# Hand.net
KiCad netlist of a schematic drawn in EAGLE
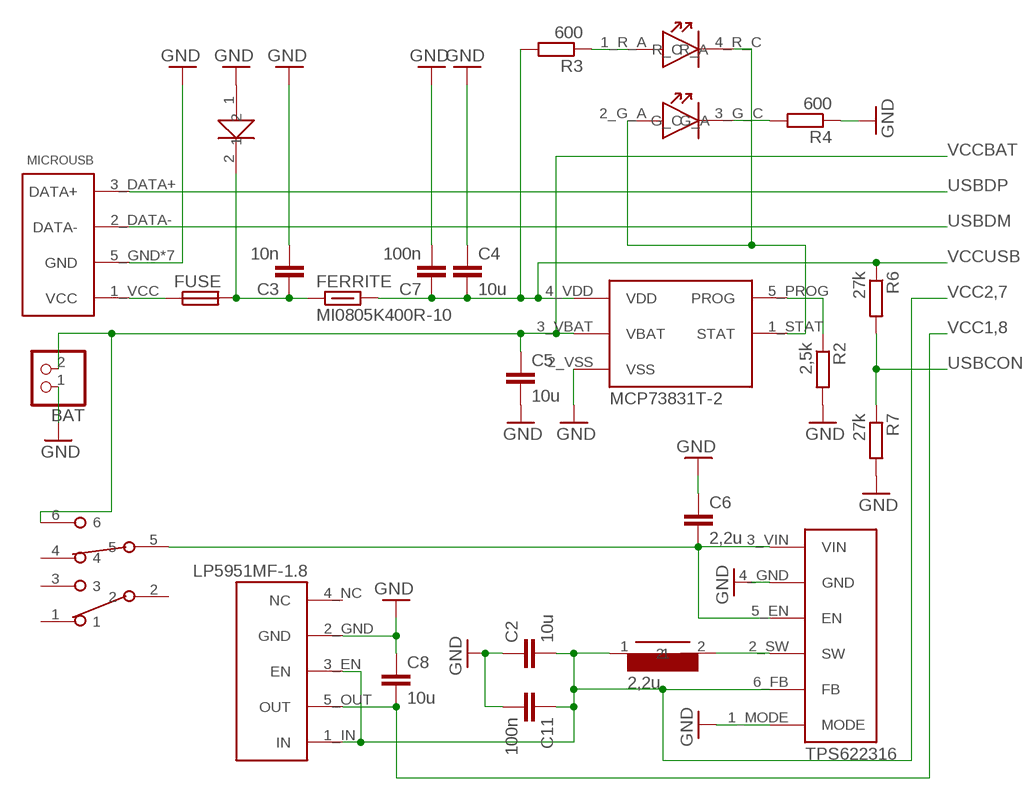
[diagram p0: schematic, sheet 1, part 1 of 2]
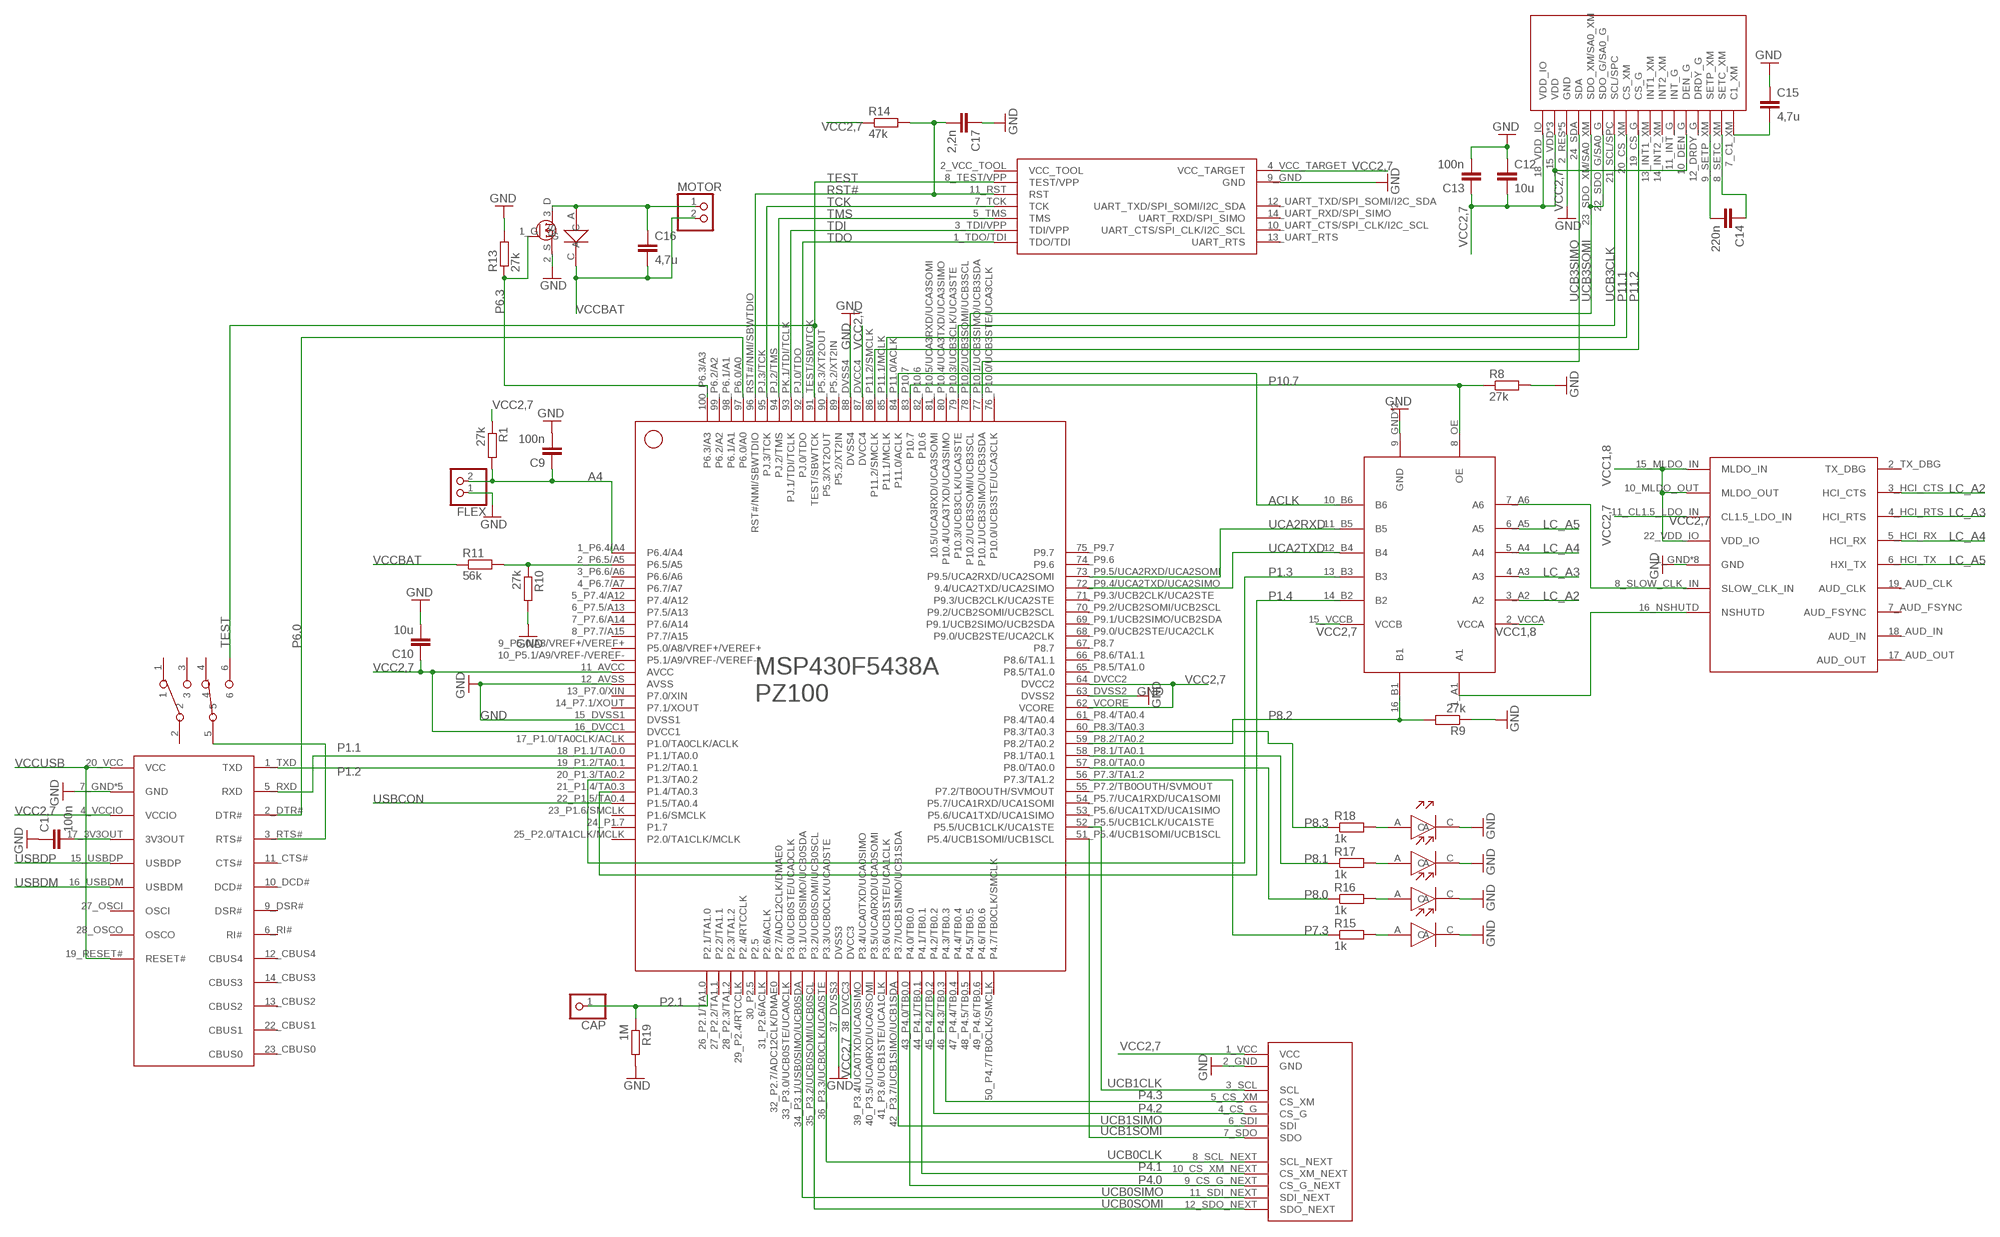
[diagram p1: schematic, sheet 1, part 2 of 2]

(export (version "E")
  (design (tool "Eeschema 10.0.6"))
  (components
    (comp (ref "BAT")
      (value "PINHD-1X2")
      (footprint "eagle-import:1X02")
      (libsource (lib "eagle-import") (part "PINHD-1X2"))
    )
    (comp (ref "C1")
      (value "100n")
      (footprint "eagle-import:C0402")
      (libsource (lib "eagle-import") (part "rclGlove_C-EUC0402"))
    )
    (comp (ref "C2")
      (value "10u")
      (footprint "eagle-import:C0805")
      (libsource (lib "eagle-import") (part "C-EUC0805"))
    )
    (comp (ref "C3")
      (value "10n")
      (footprint "eagle-import:C0402")
      (libsource (lib "eagle-import") (part "rclGlove_C-EUC0402"))
    )
    (comp (ref "C4")
      (value "10u")
      (footprint "eagle-import:C0805")
      (libsource (lib "eagle-import") (part "C-EUC0805"))
    )
    (comp (ref "C5")
      (value "10u")
      (footprint "eagle-import:C0805")
      (libsource (lib "eagle-import") (part "C-EUC0805"))
    )
    (comp (ref "C6")
      (value "2,2u")
      (footprint "eagle-import:C0805")
      (libsource (lib "eagle-import") (part "C-EUC0805"))
    )
    (comp (ref "C7")
      (value "100n")
      (footprint "eagle-import:C0402")
      (libsource (lib "eagle-import") (part "rclGlove_C-EUC0402"))
    )
    (comp (ref "C8")
      (value "10u")
      (footprint "eagle-import:C0805")
      (libsource (lib "eagle-import") (part "C-EUC0805"))
    )
    (comp (ref "C9")
      (value "100n")
      (footprint "eagle-import:C0402")
      (libsource (lib "eagle-import") (part "rclGlove_C-EUC0402"))
    )
    (comp (ref "C10")
      (value "10u")
      (footprint "eagle-import:C0805")
      (libsource (lib "eagle-import") (part "C-EUC0805"))
    )
    (comp (ref "C11")
      (value "100n")
      (footprint "eagle-import:C0402")
      (libsource (lib "eagle-import") (part "rclGlove_C-EUC0402"))
    )
    (comp (ref "C12")
      (value "10u")
      (footprint "eagle-import:C0805")
      (libsource (lib "eagle-import") (part "C-EUC0805"))
    )
    (comp (ref "C13")
      (value "100n")
      (footprint "eagle-import:C0402")
      (libsource (lib "eagle-import") (part "rclGlove_C-EUC0402"))
    )
    (comp (ref "C14")
      (value "220n")
      (footprint "eagle-import:C0402")
      (libsource (lib "eagle-import") (part "rclGlove_C-EUC0402"))
    )
    (comp (ref "C15")
      (value "4,7u")
      (footprint "eagle-import:C0805")
      (libsource (lib "eagle-import") (part "C-EUC0805"))
    )
    (comp (ref "C16")
      (value "4,7u")
      (footprint "eagle-import:C0805")
      (libsource (lib "eagle-import") (part "C-EUC0805"))
    )
    (comp (ref "C17")
      (value "2,2n")
      (footprint "eagle-import:C0603")
      (libsource (lib "eagle-import") (part "rclGlove_C-EUC0603"))
    )
    (comp (ref "CAP")
      (value "PINHD-1X1")
      (footprint "eagle-import:1X01")
      (libsource (lib "eagle-import") (part "PINHD-1X1"))
    )
    (comp (ref "FERRITE")
      (value "MI0805K400R-10")
      (footprint "eagle-import:R0603")
      (libsource (lib "eagle-import") (part "FERRITER0603"))
    )
    (comp (ref "FLEX")
      (value "PINHD-1X2")
      (footprint "eagle-import:1X02")
      (libsource (lib "eagle-import") (part "PINHD-1X2"))
    )
    (comp (ref "FUSE")
      (value "SICHERUNG")
      (footprint "eagle-import:C0603")
      (libsource (lib "eagle-import") (part "SICHERUNG"))
    )
    (comp (ref "IMU_OUT")
      (value "IMU-BUCHSE-OUT")
      (footprint "eagle-import:OUT")
      (libsource (lib "eagle-import") (part "IMU-BUCHSE-OUT"))
    )
    (comp (ref "LP5951MF-1.8")
      (value "VDDIOREGLER-SC70")
      (footprint "eagle-import:SC70")
      (libsource (lib "eagle-import") (part "VDDIOREGLER-SC70"))
    )
    (comp (ref "MCP73831T-2")
      (value "MCP73831/2-SOT-23-5")
      (footprint "eagle-import:SOT-23-5")
      (libsource (lib "eagle-import") (part "MCP73831/2-SOT-23-5"))
    )
    (comp (ref "MICROUSB")
      (value "MICRO_USB-PCB")
      (footprint "eagle-import:PCB")
      (libsource (lib "eagle-import") (part "MICRO_USB-PCB"))
    )
    (comp (ref "MOTOR")
      (value "PINHD-1X2")
      (footprint "eagle-import:1X02")
      (libsource (lib "eagle-import") (part "PINHD-1X2"))
    )
    (comp (ref "R1")
      (value "27k")
      (footprint "eagle-import:R0402")
      (libsource (lib "eagle-import") (part "R-EU_R0402"))
    )
    (comp (ref "R2")
      (value "2,5k")
      (footprint "eagle-import:R0402")
      (libsource (lib "eagle-import") (part "R-EU_R0402"))
    )
    (comp (ref "R3")
      (value "600")
      (footprint "eagle-import:R0402")
      (libsource (lib "eagle-import") (part "R-EU_R0402"))
    )
    (comp (ref "R4")
      (value "600")
      (footprint "eagle-import:R0402")
      (libsource (lib "eagle-import") (part "R-EU_R0402"))
    )
    (comp (ref "R6")
      (value "27k")
      (footprint "eagle-import:R0402")
      (libsource (lib "eagle-import") (part "R-EU_R0402"))
    )
    (comp (ref "R7")
      (value "27k")
      (footprint "eagle-import:R0402")
      (libsource (lib "eagle-import") (part "R-EU_R0402"))
    )
    (comp (ref "R8")
      (value "27k")
      (footprint "eagle-import:R0402")
      (libsource (lib "eagle-import") (part "R-EU_R0402"))
    )
    (comp (ref "R9")
      (value "27k")
      (footprint "eagle-import:R0402")
      (libsource (lib "eagle-import") (part "R-EU_R0402"))
    )
    (comp (ref "R10")
      (value "27k")
      (footprint "eagle-import:R0402")
      (libsource (lib "eagle-import") (part "R-EU_R0402"))
    )
    (comp (ref "R11")
      (value "56k")
      (footprint "eagle-import:R0402")
      (libsource (lib "eagle-import") (part "R-EU_R0402"))
    )
    (comp (ref "R13")
      (value "27k")
      (footprint "eagle-import:R0402")
      (libsource (lib "eagle-import") (part "R-EU_R0402"))
    )
    (comp (ref "R14")
      (value "47k")
      (footprint "eagle-import:R0402")
      (libsource (lib "eagle-import") (part "R-EU_R0402"))
    )
    (comp (ref "R15")
      (value "1k")
      (footprint "eagle-import:R0402")
      (libsource (lib "eagle-import") (part "R-EU_R0402"))
    )
    (comp (ref "R16")
      (value "1k")
      (footprint "eagle-import:R0402")
      (libsource (lib "eagle-import") (part "R-EU_R0402"))
    )
    (comp (ref "R17")
      (value "1k")
      (footprint "eagle-import:R0402")
      (libsource (lib "eagle-import") (part "R-EU_R0402"))
    )
    (comp (ref "R18")
      (value "1k")
      (footprint "eagle-import:R0402")
      (libsource (lib "eagle-import") (part "R-EU_R0402"))
    )
    (comp (ref "R19")
      (value "1M")
      (footprint "eagle-import:R0402")
      (libsource (lib "eagle-import") (part "R-EU_R0402"))
    )
    (comp (ref "SPULE")
      (value "2,2u")
      (footprint "eagle-import:C0603")
      (libsource (lib "eagle-import") (part "SPULE"))
    )
    (comp (ref "TPS622316")
      (value "SCHALTREGLER-R-PUSON-N6")
      (footprint "eagle-import:R-PUSON-N6")
      (libsource (lib "eagle-import") (part "SCHALTREGLER-R-PUSON-N6"))
    )
    (comp (ref "U$1")
      (value "FT232R-SSOP-28")
      (footprint "eagle-import:SSOP-28")
      (libsource (lib "eagle-import") (part "FT232R-SSOP-28"))
    )
    (comp (ref "U$2")
      (value "LSM9DS0-LGA-24")
      (footprint "eagle-import:LGA-24")
      (libsource (lib "eagle-import") (part "LSM9DS0-LGA-24"))
    )
    (comp (ref "U$4")
      (value "PAN132X")
      (footprint "eagle-import:BOARD")
      (libsource (lib "eagle-import") (part "PAN132X"))
    )
    (comp (ref "U$5")
      (value "MSP430BT5190-PZ100")
      (footprint "eagle-import:PZ100")
      (libsource (lib "eagle-import") (part "MSP430BT5190-PZ100"))
    )
    (comp (ref "U$7")
      (value "LED-PCB")
      (footprint "eagle-import:PCB")
      (libsource (lib "eagle-import") (part "LED-PCB"))
    )
    (comp (ref "U$8")
      (value "LADE-MOSFET-SOC-23")
      (footprint "eagle-import:SOT-23")
      (libsource (lib "eagle-import") (part "LADE-MOSFET-SOC-23"))
    )
    (comp (ref "U$9")
      (value "FREILAUFDIODE")
      (footprint "eagle-import:FEILAUFDIODE")
      (libsource (lib "eagle-import") (part "FREILAUFDIODE"))
    )
    (comp (ref "U$11")
      (value "ANSCHALTER-PACKAGE")
      (footprint "eagle-import:PACKAGE")
      (libsource (lib "eagle-import") (part "ANSCHALTER-PACKAGE"))
    )
    (comp (ref "U$12")
      (value "ANSCHALTER-PACKAGE")
      (footprint "eagle-import:PACKAGE")
      (libsource (lib "eagle-import") (part "ANSCHALTER-PACKAGE"))
    )
    (comp (ref "U$13")
      (value "LOGIKPEGELWANDLER-6CH")
      (footprint "eagle-import:R-PVQFN-N16")
      (libsource (lib "eagle-import") (part "LOGIKPEGELWANDLER-6CH"))
    )
    (comp (ref "U$15")
      (value "LEDMINI")
      (footprint "eagle-import:LEDMINI")
      (libsource (lib "eagle-import") (part "LEDMINI"))
    )
    (comp (ref "U$16")
      (value "JTAG-BUCHSE")
      (footprint "eagle-import:BUCHSE")
      (libsource (lib "eagle-import") (part "JTAG-BUCHSE"))
    )
    (comp (ref "U$17")
      (value "LEDMINI")
      (footprint "eagle-import:LEDMINI")
      (libsource (lib "eagle-import") (part "LEDMINI"))
    )
    (comp (ref "U$18")
      (value "LEDMINI")
      (footprint "eagle-import:LEDMINI")
      (libsource (lib "eagle-import") (part "LEDMINI"))
    )
    (comp (ref "U$19")
      (value "LEDMINI")
      (footprint "eagle-import:LEDMINI")
      (libsource (lib "eagle-import") (part "LEDMINI"))
    )
    (comp (ref "U$20")
      (value "DIODE-C0603")
      (footprint "eagle-import:C0603")
      (libsource (lib "eagle-import") (part "DIODE-C0603"))
    )
  )
  (nets
    (net (code "1") (name "/A4") (class "Default")
      (node (ref "C9") (pin "1") (pinfunction "1_1") (pintype "passive"))
      (node (ref "FLEX") (pin "2") (pinfunction "2_2") (pintype "passive"))
      (node (ref "R1") (pin "2") (pinfunction "2_2") (pintype "passive"))
      (node (ref "U$5") (pin "1_P6.4/A4") (pinfunction "P6.4/A4_1_P6.4/A4") (pintype "bidirectional"))
    )
    (net (code "2") (name "/ACLK") (class "Default")
      (node (ref "U$13") (pin "10_B6") (pinfunction "B6_10_B6") (pintype "bidirectional"))
      (node (ref "U$5") (pin "84_P11.0/ACLK") (pinfunction "P11.0/ACLK_84_P11.0/ACLK") (pintype "bidirectional"))
    )
    (net (code "3") (name "/LC_A2") (class "Default")
      (node (ref "U$13") (pin "3_A2") (pinfunction "A2_3_A2") (pintype "bidirectional"))
      (node (ref "U$4") (pin "3_HCI_CTS") (pinfunction "HCI_CTS_3_HCI_CTS") (pintype "bidirectional"))
    )
    (net (code "4") (name "/LC_A3") (class "Default")
      (node (ref "U$13") (pin "4_A3") (pinfunction "A3_4_A3") (pintype "bidirectional"))
      (node (ref "U$4") (pin "4_HCI_RTS") (pinfunction "HCI_RTS_4_HCI_RTS") (pintype "bidirectional"))
    )
    (net (code "5") (name "/LC_A4") (class "Default")
      (node (ref "U$13") (pin "5_A4") (pinfunction "A4_5_A4") (pintype "bidirectional"))
      (node (ref "U$4") (pin "5_HCI_RX") (pinfunction "HCI_RX_5_HCI_RX") (pintype "bidirectional"))
    )
    (net (code "6") (name "/LC_A5") (class "Default")
      (node (ref "U$13") (pin "6_A5") (pinfunction "A5_6_A5") (pintype "bidirectional"))
      (node (ref "U$4") (pin "6_HCI_TX") (pinfunction "HXI_TX_6_HCI_TX") (pintype "bidirectional"))
    )
    (net (code "7") (name "/P1.1") (class "Default")
      (node (ref "U$1") (pin "5_RXD") (pinfunction "RXD_5_RXD") (pintype "bidirectional"))
      (node (ref "U$5") (pin "18_P1.1/TA0.0") (pinfunction "P1.1/TA0.0_18_P1.1/TA0.0") (pintype "bidirectional"))
    )
    (net (code "8") (name "/P1.2") (class "Default")
      (node (ref "U$1") (pin "1_TXD") (pinfunction "TXD_1_TXD") (pintype "bidirectional"))
      (node (ref "U$5") (pin "19_P1.2/TA0.1") (pinfunction "P1.2/TA0.1_19_P1.2/TA0.1") (pintype "bidirectional"))
    )
    (net (code "9") (name "/P1.3") (class "Default")
      (node (ref "U$13") (pin "13_B3") (pinfunction "B3_13_B3") (pintype "bidirectional"))
      (node (ref "U$5") (pin "20_P1.3/TA0.2") (pinfunction "P1.3/TA0.2_20_P1.3/TA0.2") (pintype "bidirectional"))
    )
    (net (code "10") (name "/P1.4") (class "Default")
      (node (ref "U$13") (pin "14_B2") (pinfunction "B2_14_B2") (pintype "bidirectional"))
      (node (ref "U$5") (pin "21_P1.4/TA0.3") (pinfunction "P1.4/TA0.3_21_P1.4/TA0.3") (pintype "bidirectional"))
    )
    (net (code "11") (name "/P2.1") (class "Default")
      (node (ref "CAP") (pin "1") (pinfunction "1_1") (pintype "passive"))
      (node (ref "R19") (pin "1") (pinfunction "1_1") (pintype "passive"))
      (node (ref "U$5") (pin "26_P2.1/TA1.0") (pinfunction "P2.1/TA1.0_26_P2.1/TA1.0") (pintype "bidirectional"))
    )
    (net (code "12") (name "/P4.0") (class "Default")
      (node (ref "IMU_OUT") (pin "9_CS_G_NEXT") (pinfunction "CS_G_NEXT_9_CS_G_NEXT") (pintype "bidirectional"))
      (node (ref "U$5") (pin "43_P4.0/TB0.0") (pinfunction "P4.0/TB0.0_43_P4.0/TB0.0") (pintype "bidirectional"))
    )
    (net (code "13") (name "/P4.1") (class "Default")
      (node (ref "IMU_OUT") (pin "10_CS_XM_NEXT") (pinfunction "CS_XM_NEXT_10_CS_XM_NEXT") (pintype "bidirectional"))
      (node (ref "U$5") (pin "44_P4.1/TB0.1") (pinfunction "P4.1/TB0.1_44_P4.1/TB0.1") (pintype "bidirectional"))
    )
    (net (code "14") (name "/P4.2") (class "Default")
      (node (ref "IMU_OUT") (pin "4_CS_G") (pinfunction "CS_G_4_CS_G") (pintype "bidirectional"))
      (node (ref "U$5") (pin "45_P4.2/TB0.2") (pinfunction "P4.2/TB0.2_45_P4.2/TB0.2") (pintype "bidirectional"))
    )
    (net (code "15") (name "/P4.3") (class "Default")
      (node (ref "IMU_OUT") (pin "5_CS_XM") (pinfunction "CS_XM_5_CS_XM") (pintype "bidirectional"))
      (node (ref "U$5") (pin "46_P4.3/TB0.3") (pinfunction "P4.3/TB0.3_46_P4.3/TB0.3") (pintype "bidirectional"))
    )
    (net (code "16") (name "/P6.0") (class "Default")
      (node (ref "U$1") (pin "2_DTR#") (pinfunction "DTR#_2_DTR#") (pintype "bidirectional"))
      (node (ref "U$5") (pin "97_P6.0/A0") (pinfunction "P6.0/A0_97_P6.0/A0") (pintype "bidirectional"))
    )
    (net (code "17") (name "/P6.3") (class "Default")
      (node (ref "R13") (pin "1") (pinfunction "1_1") (pintype "passive"))
      (node (ref "U$5") (pin "100_P6.3/A3") (pinfunction "P6.3/A3_100_P6.3/A3") (pintype "bidirectional"))
      (node (ref "U$8") (pin "1_G") (pinfunction "G_1_G") (pintype "bidirectional"))
    )
    (net (code "18") (name "/P7.3") (class "Default")
      (node (ref "R15") (pin "1") (pinfunction "1_1") (pintype "passive"))
      (node (ref "U$5") (pin "56_P7.3/TA1.2") (pinfunction "P7.3/TA1.2_56_P7.3/TA1.2") (pintype "bidirectional"))
    )
    (net (code "19") (name "/P8.0") (class "Default")
      (node (ref "R16") (pin "1") (pinfunction "1_1") (pintype "passive"))
      (node (ref "U$5") (pin "57_P8.0/TA0.0") (pinfunction "P8.0/TA0.0_57_P8.0/TA0.0") (pintype "bidirectional"))
    )
    (net (code "20") (name "/P8.1") (class "Default")
      (node (ref "R17") (pin "1") (pinfunction "1_1") (pintype "passive"))
      (node (ref "U$5") (pin "58_P8.1/TA0.1") (pinfunction "P8.1/TA0.1_58_P8.1/TA0.1") (pintype "bidirectional"))
    )
    (net (code "21") (name "/P8.2") (class "Default")
      (node (ref "R9") (pin "2") (pinfunction "2_2") (pintype "passive"))
      (node (ref "U$13") (pin "16_B1") (pinfunction "B1_16_B1") (pintype "bidirectional"))
      (node (ref "U$5") (pin "59_P8.2/TA0.2") (pinfunction "P8.2/TA0.2_59_P8.2/TA0.2") (pintype "bidirectional"))
    )
    (net (code "22") (name "/P8.3") (class "Default")
      (node (ref "R18") (pin "1") (pinfunction "1_1") (pintype "passive"))
      (node (ref "U$5") (pin "60_P8.3/TA0.3") (pinfunction "P8.3/TA0.3_60_P8.3/TA0.3") (pintype "bidirectional"))
    )
    (net (code "23") (name "/P10.7") (class "Default")
      (node (ref "R8") (pin "1") (pinfunction "1_1") (pintype "passive"))
      (node (ref "U$13") (pin "8_OE") (pinfunction "OE_8_OE") (pintype "bidirectional"))
      (node (ref "U$5") (pin "83_P10.7") (pinfunction "P10.7_83_P10.7") (pintype "bidirectional"))
    )
    (net (code "24") (name "/P11.1") (class "Default")
      (node (ref "U$2") (pin "20_CS_XM") (pinfunction "CS_XM_20_CS_XM") (pintype "bidirectional"))
      (node (ref "U$5") (pin "85_P11.1/MCLK") (pinfunction "P11.1/MCLK_85_P11.1/MCLK") (pintype "bidirectional"))
    )
    (net (code "25") (name "/P11.2") (class "Default")
      (node (ref "U$2") (pin "19_CS_G") (pinfunction "CS_G_19_CS_G") (pintype "bidirectional"))
      (node (ref "U$5") (pin "86_P11.2/SMCLK") (pinfunction "P11.2/SMCLK_86_P11.2/SMCLK") (pintype "bidirectional"))
    )
    (net (code "26") (name "/RST#") (class "Default")
      (node (ref "C17") (pin "2") (pinfunction "2_2") (pintype "passive"))
      (node (ref "R14") (pin "2") (pinfunction "2_2") (pintype "passive"))
      (node (ref "U$16") (pin "11_RST") (pinfunction "RST_11_RST") (pintype "bidirectional"))
      (node (ref "U$5") (pin "96_RST#/NMI/SBWTDIO") (pinfunction "RST#/NMI/SBWTDIO_96_RST#/NMI/SBWTDIO") (pintype "bidirectional"))
    )
    (net (code "27") (name "/TCK") (class "Default")
      (node (ref "U$16") (pin "7_TCK") (pinfunction "TCK_7_TCK") (pintype "bidirectional"))
      (node (ref "U$5") (pin "95_PJ.3/TCK") (pinfunction "PJ.3/TCK_95_PJ.3/TCK") (pintype "bidirectional"))
    )
    (net (code "28") (name "/TDI") (class "Default")
      (node (ref "U$16") (pin "3_TDI/VPP") (pinfunction "TDI/VPP_3_TDI/VPP") (pintype "bidirectional"))
      (node (ref "U$5") (pin "93_PK.1/TDI/TCLK") (pinfunction "PJ.1/TDI/TCLK_93_PK.1/TDI/TCLK") (pintype "bidirectional"))
    )
    (net (code "29") (name "/TDO") (class "Default")
      (node (ref "U$16") (pin "1_TDO/TDI") (pinfunction "TDO/TDI_1_TDO/TDI") (pintype "bidirectional"))
      (node (ref "U$5") (pin "92_PJ.0/TDO") (pinfunction "PJ.0/TDO_92_PJ.0/TDO") (pintype "bidirectional"))
    )
    (net (code "30") (name "/TEST") (class "Default")
      (node (ref "U$11") (pin "6") (pinfunction "6_6") (pintype "bidirectional"))
      (node (ref "U$16") (pin "8_TEST/VPP") (pinfunction "TEST/VPP_8_TEST/VPP") (pintype "bidirectional"))
      (node (ref "U$5") (pin "91_TEST/SBWTCK") (pinfunction "TEST/SBWTCK_91_TEST/SBWTCK") (pintype "bidirectional"))
    )
    (net (code "31") (name "/TMS") (class "Default")
      (node (ref "U$16") (pin "5_TMS") (pinfunction "TMS_5_TMS") (pintype "bidirectional"))
      (node (ref "U$5") (pin "94_PJ.2/TMS") (pinfunction "PJ.2/TMS_94_PJ.2/TMS") (pintype "bidirectional"))
    )
    (net (code "32") (name "/UCA2RXD") (class "Default")
      (node (ref "U$13") (pin "11_B5") (pinfunction "B5_11_B5") (pintype "bidirectional"))
      (node (ref "U$5") (pin "73_P9.5/UCA2RXD/UCA2SOMI") (pinfunction "P9.5/UCA2RXD/UCA2SOMI_73_P9.5/UCA2RXD/UCA2SOMI") (pintype "bidirectional"))
    )
    (net (code "33") (name "/UCA2TXD") (class "Default")
      (node (ref "U$13") (pin "12_B4") (pinfunction "B4_12_B4") (pintype "bidirectional"))
      (node (ref "U$5") (pin "72_P9.4/UCA2TXD/UCA2SIMO") (pinfunction "9.4/UCA2TXD/UCA2SIMO_72_P9.4/UCA2TXD/UCA2SIMO") (pintype "bidirectional"))
    )
    (net (code "34") (name "/UCB0CLK") (class "Default")
      (node (ref "IMU_OUT") (pin "8_SCL_NEXT") (pinfunction "SCL_NEXT_8_SCL_NEXT") (pintype "bidirectional"))
      (node (ref "U$5") (pin "36_P3.3/UCB0CLK/UCA0STE") (pinfunction "P3.3/UCB0CLK/UCA0STE_36_P3.3/UCB0CLK/UCA0STE") (pintype "bidirectional"))
    )
    (net (code "35") (name "/UCB0SIMO") (class "Default")
      (node (ref "IMU_OUT") (pin "11_SDI_NEXT") (pinfunction "SDI_NEXT_11_SDI_NEXT") (pintype "bidirectional"))
      (node (ref "U$5") (pin "34_P3.1/USB0SIMO/UCB0SDA") (pinfunction "P3.1/UCB0SIMO/UCB0SDA_34_P3.1/USB0SIMO/UCB0SDA") (pintype "bidirectional"))
    )
    (net (code "36") (name "/UCB0SOMI") (class "Default")
      (node (ref "IMU_OUT") (pin "12_SDO_NEXT") (pinfunction "SDO_NEXT_12_SDO_NEXT") (pintype "bidirectional"))
      (node (ref "U$5") (pin "35_P3.2/UCB0SOMI/UCB0SCL") (pinfunction "P3.2/UCB0SOMI/UCB0SCL_35_P3.2/UCB0SOMI/UCB0SCL") (pintype "bidirectional"))
    )
    (net (code "37") (name "/UCB1CLK") (class "Default")
      (node (ref "IMU_OUT") (pin "3_SCL") (pinfunction "SCL_3_SCL") (pintype "bidirectional"))
      (node (ref "U$5") (pin "52_P5.5/UCB1CLK/UCA1STE") (pinfunction "P5.5/UCB1CLK/UCA1STE_52_P5.5/UCB1CLK/UCA1STE") (pintype "bidirectional"))
    )
    (net (code "38") (name "/UCB1SIMO") (class "Default")
      (node (ref "IMU_OUT") (pin "6_SDI") (pinfunction "SDI_6_SDI") (pintype "bidirectional"))
      (node (ref "U$5") (pin "42_P3.7/UCB1SIMO/UCB1SDA") (pinfunction "P3.7/UCB1SIMO/UCB1SDA_42_P3.7/UCB1SIMO/UCB1SDA") (pintype "bidirectional"))
    )
    (net (code "39") (name "/UCB1SOMI") (class "Default")
      (node (ref "IMU_OUT") (pin "7_SDO") (pinfunction "SDO_7_SDO") (pintype "bidirectional"))
      (node (ref "U$5") (pin "51_P5.4/UCB1SOMI/UCB1SCL") (pinfunction "P5.4/UCB1SOMI/UCB1SCL_51_P5.4/UCB1SOMI/UCB1SCL") (pintype "bidirectional"))
    )
    (net (code "40") (name "/UCB3CLK") (class "Default")
      (node (ref "U$2") (pin "21_SCL/SPC") (pinfunction "SCL/SPC_21_SCL/SPC") (pintype "bidirectional"))
      (node (ref "U$5") (pin "79_P10.3/UCB3CLK/UCA3STE") (pinfunction "P10.3/UCB3CLK/UCA3STE_79_P10.3/UCB3CLK/UCA3STE") (pintype "bidirectional"))
    )
    (net (code "41") (name "/UCB3SIMO") (class "Default")
      (node (ref "U$2") (pin "24_SDA") (pinfunction "SDA_24_SDA") (pintype "bidirectional"))
      (node (ref "U$5") (pin "77_P10.1/UCB3SIMO/UCB3SDA") (pinfunction "P10.1/UCB3SIMO/UCB3SDA_77_P10.1/UCB3SIMO/UCB3SDA") (pintype "bidirectional"))
    )
    (net (code "42") (name "/UCB3SOMI") (class "Default")
      (node (ref "U$2") (pin "22_SDO_G/SA0_G") (pinfunction "SDO_G/SA0_G_22_SDO_G/SA0_G") (pintype "bidirectional"))
      (node (ref "U$2") (pin "23_SDO_XM/SA0_XM") (pinfunction "SDO_XM/SA0_XM_23_SDO_XM/SA0_XM") (pintype "bidirectional"))
      (node (ref "U$5") (pin "78_P10.2/UCB3SOMI/UCB3SCL") (pinfunction "P10.2/UCB3SOMI/UCB3SCL_78_P10.2/UCB3SOMI/UCB3SCL") (pintype "bidirectional"))
    )
    (net (code "43") (name "/USBCON") (class "Default")
      (node (ref "R6") (pin "2") (pinfunction "2_2") (pintype "passive"))
      (node (ref "R7") (pin "1") (pinfunction "1_1") (pintype "passive"))
      (node (ref "U$5") (pin "22_P1.5/TA0.4") (pinfunction "P1.5/TA0.4_22_P1.5/TA0.4") (pintype "bidirectional"))
    )
    (net (code "44") (name "/USBDM") (class "Default")
      (node (ref "MICROUSB") (pin "2_DATA-") (pinfunction "DATA-_2_DATA-") (pintype "bidirectional"))
      (node (ref "U$1") (pin "16_USBDM") (pinfunction "USBDM_16_USBDM") (pintype "bidirectional"))
    )
    (net (code "45") (name "/USBDP") (class "Default")
      (node (ref "MICROUSB") (pin "3_DATA+") (pinfunction "DATA+_3_DATA+") (pintype "bidirectional"))
      (node (ref "U$1") (pin "15_USBDP") (pinfunction "USBDP_15_USBDP") (pintype "bidirectional"))
    )
    (net (code "46") (name "/VCC1,8") (class "Default")
      (node (ref "C8") (pin "2") (pinfunction "2_2") (pintype "passive"))
      (node (ref "LP5951MF-1.8") (pin "5_OUT") (pinfunction "OUT_5_OUT") (pintype "bidirectional"))
      (node (ref "U$13") (pin "2_VCCA") (pinfunction "VCCA_2_VCCA") (pintype "bidirectional"))
      (node (ref "U$4") (pin "10_MLDO_OUT") (pinfunction "MLDO_OUT_10_MLDO_OUT") (pintype "bidirectional"))
      (node (ref "U$4") (pin "15_MLDO_IN") (pinfunction "MLDO_IN_15_MLDO_IN") (pintype "bidirectional"))
      (node (ref "U$4") (pin "22_VDD_IO") (pinfunction "VDD_IO_22_VDD_IO") (pintype "bidirectional"))
    )
    (net (code "47") (name "/VCC2,7") (class "Default")
      (node (ref "C10") (pin "1") (pinfunction "1_1") (pintype "passive"))
      (node (ref "C11") (pin "1") (pinfunction "1_1") (pintype "passive"))
      (node (ref "C12") (pin "2") (pinfunction "2_2") (pintype "passive"))
      (node (ref "C13") (pin "1") (pinfunction "1_1") (pintype "passive"))
      (node (ref "C2") (pin "2") (pinfunction "2_2") (pintype "passive"))
      (node (ref "IMU_OUT") (pin "1_VCC") (pinfunction "VCC_1_VCC") (pintype "bidirectional"))
      (node (ref "LP5951MF-1.8") (pin "1_IN") (pinfunction "IN_1_IN") (pintype "bidirectional"))
      (node (ref "LP5951MF-1.8") (pin "3_EN") (pinfunction "EN_3_EN") (pintype "bidirectional"))
      (node (ref "R1") (pin "1") (pinfunction "1_1") (pintype "passive"))
      (node (ref "R14") (pin "1") (pinfunction "1_1") (pintype "passive"))
      (node (ref "SPULE") (pin "1") (pinfunction "1_1") (pintype "bidirectional"))
      (node (ref "TPS622316") (pin "6_FB") (pinfunction "FB_6_FB") (pintype "bidirectional"))
      (node (ref "U$1") (pin "4_VCCIO") (pinfunction "VCCIO_4_VCCIO") (pintype "bidirectional"))
      (node (ref "U$13") (pin "15_VCCB") (pinfunction "VCCB_15_VCCB") (pintype "bidirectional"))
      (node (ref "U$16") (pin "4_VCC_TARGET") (pinfunction "VCC_TARGET_4_VCC_TARGET") (pintype "bidirectional"))
      (node (ref "U$2") (pin "10_DEN_G") (pinfunction "DEN_G_10_DEN_G") (pintype "bidirectional"))
      (node (ref "U$2") (pin "15_VDD") (pinfunction "VDD_15_VDD") (pintype "bidirectional"))
      (node (ref "U$2") (pin "16_VDD") (pinfunction "VDD_16_VDD") (pintype "bidirectional"))
      (node (ref "U$2") (pin "17_VDD") (pinfunction "VDD_17_VDD") (pintype "bidirectional"))
      (node (ref "U$2") (pin "18_VDD_IO") (pinfunction "VDD_IO_18_VDD_IO") (pintype "bidirectional"))
      (node (ref "U$4") (pin "11_CL1.5_LDO_IN") (pinfunction "CL1.5_LDO_IN_11_CL1.5_LDO_IN") (pintype "bidirectional"))
      (node (ref "U$5") (pin "11_AVCC") (pinfunction "AVCC_11_AVCC") (pintype "bidirectional"))
      (node (ref "U$5") (pin "16_DVCC1") (pinfunction "DVCC1_16_DVCC1") (pintype "bidirectional"))
      (node (ref "U$5") (pin "38_DVCC3") (pinfunction "DVCC3_38_DVCC3") (pintype "bidirectional"))
      (node (ref "U$5") (pin "62_VCORE") (pinfunction "VCORE_62_VCORE") (pintype "bidirectional"))
      (node (ref "U$5") (pin "64_DVCC2") (pinfunction "DVCC2_64_DVCC2") (pintype "bidirectional"))
      (node (ref "U$5") (pin "87_DVCC4") (pinfunction "DVCC4_87_DVCC4") (pintype "bidirectional"))
    )
    (net (code "48") (name "/VCCBAT") (class "Default")
      (node (ref "BAT") (pin "2") (pinfunction "2_2") (pintype "passive"))
      (node (ref "C16") (pin "2") (pinfunction "2_2") (pintype "passive"))
      (node (ref "C5") (pin "1") (pinfunction "1_1") (pintype "passive"))
      (node (ref "MCP73831T-2") (pin "3_VBAT") (pinfunction "VBAT_3_VBAT") (pintype "bidirectional"))
      (node (ref "MOTOR") (pin "2") (pinfunction "2_2") (pintype "passive"))
      (node (ref "R11") (pin "1") (pinfunction "1_1") (pintype "passive"))
      (node (ref "U$12") (pin "6") (pinfunction "6_6") (pintype "bidirectional"))
      (node (ref "U$9") (pin "C") (pinfunction "C_C") (pintype "bidirectional"))
    )
    (net (code "49") (name "/VCCUSB") (class "Default")
      (node (ref "C4") (pin "2") (pinfunction "2_2") (pintype "passive"))
      (node (ref "C7") (pin "1") (pinfunction "1_1") (pintype "passive"))
      (node (ref "FERRITE") (pin "2") (pinfunction "2_2") (pintype "passive"))
      (node (ref "MCP73831T-2") (pin "4_VDD") (pinfunction "VDD_4_VDD") (pintype "bidirectional"))
      (node (ref "R3") (pin "2") (pinfunction "2_2") (pintype "passive"))
      (node (ref "R6") (pin "1") (pinfunction "1_1") (pintype "passive"))
      (node (ref "U$1") (pin "19_RESET#") (pinfunction "RESET#_19_RESET#") (pintype "bidirectional"))
      (node (ref "U$1") (pin "20_VCC") (pinfunction "VCC_20_VCC") (pintype "bidirectional"))
    )
    (net (code "50") (name "GND") (class "Default")
      (node (ref "BAT") (pin "1") (pinfunction "1_1") (pintype "passive"))
      (node (ref "C1") (pin "1") (pinfunction "1_1") (pintype "passive"))
      (node (ref "C10") (pin "2") (pinfunction "2_2") (pintype "passive"))
      (node (ref "C11") (pin "2") (pinfunction "2_2") (pintype "passive"))
      (node (ref "C12") (pin "1") (pinfunction "1_1") (pintype "passive"))
      (node (ref "C13") (pin "2") (pinfunction "2_2") (pintype "passive"))
      (node (ref "C15") (pin "1") (pinfunction "1_1") (pintype "passive"))
      (node (ref "C17") (pin "1") (pinfunction "1_1") (pintype "passive"))
      (node (ref "C2") (pin "1") (pinfunction "1_1") (pintype "passive"))
      (node (ref "C3") (pin "2") (pinfunction "2_2") (pintype "passive"))
      (node (ref "C4") (pin "1") (pinfunction "1_1") (pintype "passive"))
      (node (ref "C5") (pin "2") (pinfunction "2_2") (pintype "passive"))
      (node (ref "C6") (pin "1") (pinfunction "1_1") (pintype "passive"))
      (node (ref "C7") (pin "2") (pinfunction "2_2") (pintype "passive"))
      (node (ref "C8") (pin "1") (pinfunction "1_1") (pintype "passive"))
      (node (ref "C9") (pin "2") (pinfunction "2_2") (pintype "passive"))
      (node (ref "FLEX") (pin "1") (pinfunction "1_1") (pintype "passive"))
      (node (ref "IMU_OUT") (pin "2_GND") (pinfunction "GND_2_GND") (pintype "bidirectional"))
      (node (ref "LP5951MF-1.8") (pin "2_GND") (pinfunction "GND_2_GND") (pintype "bidirectional"))
      (node (ref "MCP73831T-2") (pin "2_VSS") (pinfunction "VSS_2_VSS") (pintype "bidirectional"))
      (node (ref "MICROUSB") (pin "5_GND") (pinfunction "GND_5_GND") (pintype "bidirectional"))
      (node (ref "MICROUSB") (pin "EP_1") (pinfunction "GND_EP_1") (pintype "bidirectional"))
      (node (ref "MICROUSB") (pin "EP_2") (pinfunction "GND_EP_2") (pintype "bidirectional"))
      (node (ref "MICROUSB") (pin "EP_3") (pinfunction "GND_EP_3") (pintype "bidirectional"))
      (node (ref "MICROUSB") (pin "EP_4") (pinfunction "GND_EP_4") (pintype "bidirectional"))
      (node (ref "MICROUSB") (pin "P$1") (pinfunction "GND_P$1") (pintype "bidirectional"))
      (node (ref "MICROUSB") (pin "P$2") (pinfunction "GND_P$2") (pintype "bidirectional"))
      (node (ref "R10") (pin "2") (pinfunction "2_2") (pintype "passive"))
      (node (ref "R13") (pin "2") (pinfunction "2_2") (pintype "passive"))
      (node (ref "R19") (pin "2") (pinfunction "2_2") (pintype "passive"))
      (node (ref "R2") (pin "2") (pinfunction "2_2") (pintype "passive"))
      (node (ref "R4") (pin "1") (pinfunction "1_1") (pintype "passive"))
      (node (ref "R7") (pin "2") (pinfunction "2_2") (pintype "passive"))
      (node (ref "R8") (pin "2") (pinfunction "2_2") (pintype "passive"))
      (node (ref "R9") (pin "1") (pinfunction "1_1") (pintype "passive"))
      (node (ref "TPS622316") (pin "1_MODE") (pinfunction "MODE_1_MODE") (pintype "bidirectional"))
      (node (ref "TPS622316") (pin "4_GND") (pinfunction "GND_4_GND") (pintype "bidirectional"))
      (node (ref "U$1") (pin "18_GND") (pinfunction "GND_18_GND") (pintype "bidirectional"))
      (node (ref "U$1") (pin "21_GND") (pinfunction "GND_21_GND") (pintype "bidirectional"))
      (node (ref "U$1") (pin "25_AGND") (pinfunction "GND_25_AGND") (pintype "bidirectional"))
      (node (ref "U$1") (pin "26_TEST") (pinfunction "GND_26_TEST") (pintype "bidirectional"))
      (node (ref "U$1") (pin "7_GND") (pinfunction "GND_7_GND") (pintype "bidirectional"))
      (node (ref "U$13") (pin "9_GND") (pinfunction "GND_9_GND") (pintype "bidirectional"))
      (node (ref "U$13") (pin "PAD") (pinfunction "GND_PAD") (pintype "bidirectional"))
      (node (ref "U$15") (pin "C") (pinfunction "C_C") (pintype "bidirectional"))
      (node (ref "U$16") (pin "9_GND") (pinfunction "GND_9_GND") (pintype "bidirectional"))
      (node (ref "U$17") (pin "C") (pinfunction "C_C") (pintype "bidirectional"))
      (node (ref "U$18") (pin "C") (pinfunction "C_C") (pintype "bidirectional"))
      (node (ref "U$19") (pin "C") (pinfunction "C_C") (pintype "bidirectional"))
      (node (ref "U$2") (pin "2_RES") (pinfunction "GND_2_RES") (pintype "bidirectional"))
      (node (ref "U$2") (pin "3_RES") (pinfunction "GND_3_RES") (pintype "bidirectional"))
      (node (ref "U$2") (pin "4_RES") (pinfunction "GND_4_RES") (pintype "bidirectional"))
      (node (ref "U$2") (pin "5_GND") (pinfunction "GND_5_GND") (pintype "bidirectional"))
      (node (ref "U$2") (pin "6_GND") (pinfunction "GND_6_GND") (pintype "bidirectional"))
      (node (ref "U$20") (pin "1") (pinfunction "1_1") (pintype "bidirectional"))
      (node (ref "U$4") (pin "12_GND") (pinfunction "GND_12_GND") (pintype "bidirectional"))
      (node (ref "U$4") (pin "14_GND") (pinfunction "GND_14_GND") (pintype "bidirectional"))
      (node (ref "U$4") (pin "1_GND") (pinfunction "GND_1_GND") (pintype "bidirectional"))
      (node (ref "U$4") (pin "20_GND") (pinfunction "GND_20_GND") (pintype "bidirectional"))
      (node (ref "U$4") (pin "A_GND") (pinfunction "GND_A_GND") (pintype "bidirectional"))
      (node (ref "U$4") (pin "B_GND") (pinfunction "GND_B_GND") (pintype "bidirectional"))
      (node (ref "U$4") (pin "C_GND") (pinfunction "GND_C_GND") (pintype "bidirectional"))
      (node (ref "U$4") (pin "D_GND") (pinfunction "GND_D_GND") (pintype "bidirectional"))
      (node (ref "U$5") (pin "12_AVSS") (pinfunction "AVSS_12_AVSS") (pintype "bidirectional"))
      (node (ref "U$5") (pin "15_DVSS1") (pinfunction "DVSS1_15_DVSS1") (pintype "bidirectional"))
      (node (ref "U$5") (pin "37_DVSS3") (pinfunction "DVSS3_37_DVSS3") (pintype "bidirectional"))
      (node (ref "U$5") (pin "63_DVSS2") (pinfunction "DVSS2_63_DVSS2") (pintype "bidirectional"))
      (node (ref "U$5") (pin "88_DVSS4") (pinfunction "DVSS4_88_DVSS4") (pintype "bidirectional"))
      (node (ref "U$8") (pin "2_S") (pinfunction "S_2_S") (pintype "bidirectional"))
    )
    (net (code "51") (name "Net-(C3-Pad1)") (class "Default")
      (node (ref "C3") (pin "1") (pinfunction "1_1") (pintype "passive"))
      (node (ref "FERRITE") (pin "1") (pinfunction "1_1") (pintype "passive"))
      (node (ref "FUSE") (pin "2") (pinfunction "2_2") (pintype "passive"))
      (node (ref "U$20") (pin "2") (pinfunction "2_2") (pintype "bidirectional"))
    )
    (net (code "52") (name "Net-(MCP73831T-2-PROG)") (class "Default")
      (node (ref "MCP73831T-2") (pin "5_PROG") (pinfunction "PROG_5_PROG") (pintype "bidirectional"))
      (node (ref "R2") (pin "1") (pinfunction "1_1") (pintype "passive"))
    )
    (net (code "53") (name "Net-(MCP73831T-2-STAT)") (class "Default")
      (node (ref "MCP73831T-2") (pin "1_STAT") (pinfunction "STAT_1_STAT") (pintype "bidirectional"))
      (node (ref "U$7") (pin "2_G_A") (pinfunction "G_A_2_G_A") (pintype "bidirectional"))
      (node (ref "U$7") (pin "4_R_C") (pinfunction "R_C_4_R_C") (pintype "bidirectional"))
    )
    (net (code "54") (name "Net-(MICROUSB-VCC)") (class "Default")
      (node (ref "FUSE") (pin "1") (pinfunction "1_1") (pintype "passive"))
      (node (ref "MICROUSB") (pin "1_VCC") (pinfunction "VCC_1_VCC") (pintype "bidirectional"))
    )
    (net (code "55") (name "Net-(R15-Pad2)") (class "Default")
      (node (ref "R15") (pin "2") (pinfunction "2_2") (pintype "passive"))
      (node (ref "U$19") (pin "A") (pinfunction "A_A") (pintype "bidirectional"))
    )
    (net (code "56") (name "Net-(R16-Pad2)") (class "Default")
      (node (ref "R16") (pin "2") (pinfunction "2_2") (pintype "passive"))
      (node (ref "U$18") (pin "A") (pinfunction "A_A") (pintype "bidirectional"))
    )
    (net (code "57") (name "Net-(R17-Pad2)") (class "Default")
      (node (ref "R17") (pin "2") (pinfunction "2_2") (pintype "passive"))
      (node (ref "U$17") (pin "A") (pinfunction "A_A") (pintype "bidirectional"))
    )
    (net (code "58") (name "Net-(R18-Pad2)") (class "Default")
      (node (ref "R18") (pin "2") (pinfunction "2_2") (pintype "passive"))
      (node (ref "U$15") (pin "A") (pinfunction "A_A") (pintype "bidirectional"))
    )
    (net (code "59") (name "Net-(TPS622316-EN)") (class "Default")
      (node (ref "C6") (pin "2") (pinfunction "2_2") (pintype "passive"))
      (node (ref "TPS622316") (pin "3_VIN") (pinfunction "VIN_3_VIN") (pintype "bidirectional"))
      (node (ref "TPS622316") (pin "5_EN") (pinfunction "EN_5_EN") (pintype "bidirectional"))
      (node (ref "U$12") (pin "5") (pinfunction "5_5") (pintype "bidirectional"))
    )
    (net (code "60") (name "Net-(TPS622316-SW)") (class "Default")
      (node (ref "SPULE") (pin "2") (pinfunction "2_2") (pintype "bidirectional"))
      (node (ref "TPS622316") (pin "2_SW") (pinfunction "SW_2_SW") (pintype "bidirectional"))
    )
    (net (code "61") (name "Net-(U$1-3V3OUT)") (class "Default")
      (node (ref "C1") (pin "2") (pinfunction "2_2") (pintype "passive"))
      (node (ref "U$1") (pin "17_3V3OUT") (pinfunction "3V3OUT_17_3V3OUT") (pintype "bidirectional"))
    )
    (net (code "62") (name "Net-(U$1-RTS#)") (class "Default")
      (node (ref "U$1") (pin "3_RTS#") (pinfunction "RTS#_3_RTS#") (pintype "bidirectional"))
      (node (ref "U$11") (pin "5") (pinfunction "5_5") (pintype "bidirectional"))
    )
    (net (code "63") (name "Net-(U$2-C1_XM)") (class "Default")
      (node (ref "C15") (pin "2") (pinfunction "2_2") (pintype "passive"))
      (node (ref "U$2") (pin "7_C1_XM") (pinfunction "C1_XM_7_C1_XM") (pintype "bidirectional"))
    )
    (net (code "64") (name "Net-(U$2-SETC_XM)") (class "Default")
      (node (ref "C14") (pin "1") (pinfunction "1_1") (pintype "passive"))
      (node (ref "U$2") (pin "8_SETC_XM") (pinfunction "SETC_XM_8_SETC_XM") (pintype "bidirectional"))
    )
    (net (code "65") (name "Net-(U$2-SETP_XM)") (class "Default")
      (node (ref "C14") (pin "2") (pinfunction "2_2") (pintype "passive"))
      (node (ref "U$2") (pin "9_SETP_XM") (pinfunction "SETP_XM_9_SETP_XM") (pintype "bidirectional"))
    )
    (net (code "66") (name "Net-(U$5-P6.5{slash}A5)") (class "Default")
      (node (ref "R10") (pin "1") (pinfunction "1_1") (pintype "passive"))
      (node (ref "R11") (pin "2") (pinfunction "2_2") (pintype "passive"))
      (node (ref "U$5") (pin "2_P6.5/A5") (pinfunction "P6.5/A5_2_P6.5/A5") (pintype "bidirectional"))
    )
    (net (code "67") (name "Net-(U$7-G_C)") (class "Default")
      (node (ref "R4") (pin "2") (pinfunction "2_2") (pintype "passive"))
      (node (ref "U$7") (pin "3_G_C") (pinfunction "G_C_3_G_C") (pintype "bidirectional"))
    )
    (net (code "68") (name "Net-(U$7-R_A)") (class "Default")
      (node (ref "R3") (pin "1") (pinfunction "1_1") (pintype "passive"))
      (node (ref "U$7") (pin "1_R_A") (pinfunction "R_A_1_R_A") (pintype "bidirectional"))
    )
    (net (code "69") (name "Net-(U$8-D)") (class "Default")
      (node (ref "C16") (pin "1") (pinfunction "1_1") (pintype "passive"))
      (node (ref "MOTOR") (pin "1") (pinfunction "1_1") (pintype "passive"))
      (node (ref "U$8") (pin "3_D") (pinfunction "D_3_D") (pintype "bidirectional"))
      (node (ref "U$9") (pin "A") (pinfunction "A_A") (pintype "bidirectional"))
    )
    (net (code "70") (name "Net-(U$13-A1)") (class "Default")
      (node (ref "U$13") (pin "1_A1") (pinfunction "A1_1_A1") (pintype "bidirectional"))
      (node (ref "U$4") (pin "16_NSHUTD") (pinfunction "NSHUTD_16_NSHUTD") (pintype "bidirectional"))
    )
    (net (code "71") (name "Net-(U$13-A6)") (class "Default")
      (node (ref "U$13") (pin "7_A6") (pinfunction "A6_7_A6") (pintype "bidirectional"))
      (node (ref "U$4") (pin "8_SLOW_CLK_IN") (pinfunction "SLOW_CLK_IN_8_SLOW_CLK_IN") (pintype "bidirectional"))
    )
    (net (code "72") (name "unconnected-(LP5951MF-1.8-NC-Pad4_NC)") (class "Default")
      (node (ref "LP5951MF-1.8") (pin "4_NC") (pinfunction "NC_4_NC") (pintype "bidirectional"))
    )
    (net (code "73") (name "unconnected-(U$1-CBUS0-Pad23_CBUS0)") (class "Default")
      (node (ref "U$1") (pin "23_CBUS0") (pinfunction "CBUS0_23_CBUS0") (pintype "bidirectional"))
    )
    (net (code "74") (name "unconnected-(U$1-CBUS1-Pad22_CBUS1)") (class "Default")
      (node (ref "U$1") (pin "22_CBUS1") (pinfunction "CBUS1_22_CBUS1") (pintype "bidirectional"))
    )
    (net (code "75") (name "unconnected-(U$1-CBUS2-Pad13_CBUS2)") (class "Default")
      (node (ref "U$1") (pin "13_CBUS2") (pinfunction "CBUS2_13_CBUS2") (pintype "bidirectional"))
    )
    (net (code "76") (name "unconnected-(U$1-CBUS3-Pad14_CBUS3)") (class "Default")
      (node (ref "U$1") (pin "14_CBUS3") (pinfunction "CBUS3_14_CBUS3") (pintype "bidirectional"))
    )
    (net (code "77") (name "unconnected-(U$1-CBUS4-Pad12_CBUS4)") (class "Default")
      (node (ref "U$1") (pin "12_CBUS4") (pinfunction "CBUS4_12_CBUS4") (pintype "bidirectional"))
    )
    (net (code "78") (name "unconnected-(U$1-CTS#-Pad11_CTS#)") (class "Default")
      (node (ref "U$1") (pin "11_CTS#") (pinfunction "CTS#_11_CTS#") (pintype "bidirectional"))
    )
    (net (code "79") (name "unconnected-(U$1-DCD#-Pad10_DCD#)") (class "Default")
      (node (ref "U$1") (pin "10_DCD#") (pinfunction "DCD#_10_DCD#") (pintype "bidirectional"))
    )
    (net (code "80") (name "unconnected-(U$1-DSR#-Pad9_DSR#)") (class "Default")
      (node (ref "U$1") (pin "9_DSR#") (pinfunction "DSR#_9_DSR#") (pintype "bidirectional"))
    )
    (net (code "81") (name "unconnected-(U$1-OSCI-Pad27_OSCI)") (class "Default")
      (node (ref "U$1") (pin "27_OSCI") (pinfunction "OSCI_27_OSCI") (pintype "bidirectional"))
    )
    (net (code "82") (name "unconnected-(U$1-OSCO-Pad28_OSCO)") (class "Default")
      (node (ref "U$1") (pin "28_OSCO") (pinfunction "OSCO_28_OSCO") (pintype "bidirectional"))
    )
    (net (code "83") (name "unconnected-(U$1-RI#-Pad6_RI#)") (class "Default")
      (node (ref "U$1") (pin "6_RI#") (pinfunction "RI#_6_RI#") (pintype "bidirectional"))
    )
    (net (code "84") (name "unconnected-(U$2-DRDY_G-Pad12_DRDY_G)") (class "Default")
      (node (ref "U$2") (pin "12_DRDY_G") (pinfunction "DRDY_G_12_DRDY_G") (pintype "bidirectional"))
    )
    (net (code "85") (name "unconnected-(U$2-INT1_XM-Pad13_INT1_XM)") (class "Default")
      (node (ref "U$2") (pin "13_INT1_XM") (pinfunction "INT1_XM_13_INT1_XM") (pintype "bidirectional"))
    )
    (net (code "86") (name "unconnected-(U$2-INT2_XM-Pad14_INT2_XM)") (class "Default")
      (node (ref "U$2") (pin "14_INT2_XM") (pinfunction "INT2_XM_14_INT2_XM") (pintype "bidirectional"))
    )
    (net (code "87") (name "unconnected-(U$2-INT_G-Pad11_INT_G)") (class "Default")
      (node (ref "U$2") (pin "11_INT_G") (pinfunction "INT_G_11_INT_G") (pintype "bidirectional"))
    )
    (net (code "88") (name "unconnected-(U$4-AUD_CLK-Pad19_AUD_CLK)") (class "Default")
      (node (ref "U$4") (pin "19_AUD_CLK") (pinfunction "AUD_CLK_19_AUD_CLK") (pintype "bidirectional"))
    )
    (net (code "89") (name "unconnected-(U$4-AUD_FSYNC-Pad7_AUD_FSYNC)") (class "Default")
      (node (ref "U$4") (pin "7_AUD_FSYNC") (pinfunction "AUD_FSYNC_7_AUD_FSYNC") (pintype "bidirectional"))
    )
    (net (code "90") (name "unconnected-(U$4-AUD_IN-Pad18_AUD_IN)") (class "Default")
      (node (ref "U$4") (pin "18_AUD_IN") (pinfunction "AUD_IN_18_AUD_IN") (pintype "bidirectional"))
    )
    (net (code "91") (name "unconnected-(U$4-AUD_OUT-Pad17_AUD_OUT)") (class "Default")
      (node (ref "U$4") (pin "17_AUD_OUT") (pinfunction "AUD_OUT_17_AUD_OUT") (pintype "bidirectional"))
    )
    (net (code "92") (name "unconnected-(U$4-TX_DBG-Pad2_TX_DBG)") (class "Default")
      (node (ref "U$4") (pin "2_TX_DBG") (pinfunction "TX_DBG_2_TX_DBG") (pintype "bidirectional"))
    )
    (net (code "93") (name "unconnected-(U$5-10.5{slash}UCA3RXD{slash}UCA3SOMI-Pad81_P10.5{slash}UCA3RXD{slash}UCA3SOMI)") (class "Default")
      (node (ref "U$5") (pin "81_P10.5/UCA3RXD/UCA3SOMI") (pinfunction "10.5/UCA3RXD/UCA3SOMI_81_P10.5/UCA3RXD/UCA3SOMI") (pintype "bidirectional"))
    )
    (net (code "94") (name "unconnected-(U$5-P1.0{slash}TA0CLK{slash}ACLK-Pad17_P1.0{slash}TA0CLK{slash}ACLK)") (class "Default")
      (node (ref "U$5") (pin "17_P1.0/TA0CLK/ACLK") (pinfunction "P1.0/TA0CLK/ACLK_17_P1.0/TA0CLK/ACLK") (pintype "bidirectional"))
    )
    (net (code "95") (name "unconnected-(U$5-P1.6{slash}SMCLK-Pad23_P1.6{slash}SMCLK)") (class "Default")
      (node (ref "U$5") (pin "23_P1.6/SMCLK") (pinfunction "P1.6/SMCLK_23_P1.6/SMCLK") (pintype "bidirectional"))
    )
    (net (code "96") (name "unconnected-(U$5-P1.7-Pad24_P1.7)") (class "Default")
      (node (ref "U$5") (pin "24_P1.7") (pinfunction "P1.7_24_P1.7") (pintype "bidirectional"))
    )
    (net (code "97") (name "unconnected-(U$5-P2.0{slash}TA1CLK{slash}MCLK-Pad25_P2.0{slash}TA1CLK{slash}MCLK)") (class "Default")
      (node (ref "U$5") (pin "25_P2.0/TA1CLK/MCLK") (pinfunction "P2.0/TA1CLK/MCLK_25_P2.0/TA1CLK/MCLK") (pintype "bidirectional"))
    )
    (net (code "98") (name "unconnected-(U$5-P2.2{slash}TA1.1-Pad27_P2.2{slash}TA1.1)") (class "Default")
      (node (ref "U$5") (pin "27_P2.2/TA1.1") (pinfunction "P2.2/TA1.1_27_P2.2/TA1.1") (pintype "bidirectional"))
    )
    (net (code "99") (name "unconnected-(U$5-P2.3{slash}TA1.2-Pad28_P2.3{slash}TA1.2)") (class "Default")
      (node (ref "U$5") (pin "28_P2.3/TA1.2") (pinfunction "P2.3/TA1.2_28_P2.3/TA1.2") (pintype "bidirectional"))
    )
    (net (code "100") (name "unconnected-(U$5-P2.4{slash}RTCCLK-Pad29_P2.4{slash}RTCCLK)") (class "Default")
      (node (ref "U$5") (pin "29_P2.4/RTCCLK") (pinfunction "P2.4/RTCCLK_29_P2.4/RTCCLK") (pintype "bidirectional"))
    )
    (net (code "101") (name "unconnected-(U$5-P2.5-Pad30_P2.5)") (class "Default")
      (node (ref "U$5") (pin "30_P2.5") (pinfunction "P2.5_30_P2.5") (pintype "bidirectional"))
    )
    (net (code "102") (name "unconnected-(U$5-P2.6{slash}ACLK-Pad31_P2.6{slash}ACLK)") (class "Default")
      (node (ref "U$5") (pin "31_P2.6/ACLK") (pinfunction "P2.6/ACLK_31_P2.6/ACLK") (pintype "bidirectional"))
    )
    (net (code "103") (name "unconnected-(U$5-P2.7{slash}ADC12CLK{slash}DMAE0-Pad32_P2.7{slash}ADC12CLK{slash}DMAE0)") (class "Default")
      (node (ref "U$5") (pin "32_P2.7/ADC12CLK/DMAE0") (pinfunction "P2.7/ADC12CLK/DMAE0_32_P2.7/ADC12CLK/DMAE0") (pintype "bidirectional"))
    )
    (net (code "104") (name "unconnected-(U$5-P3.0{slash}UCB0STE{slash}UCA0CLK-Pad33_P3.0{slash}UCB0STE{slash}UCA0CLK)") (class "Default")
      (node (ref "U$5") (pin "33_P3.0/UCB0STE/UCA0CLK") (pinfunction "P3.0/UCB0STE/UCA0CLK_33_P3.0/UCB0STE/UCA0CLK") (pintype "bidirectional"))
    )
    (net (code "105") (name "unconnected-(U$5-P3.4{slash}UCA0TXD{slash}UCA0SIMO-Pad39_P3.4{slash}UCA0TXD{slash}UCA0SIMO)") (class "Default")
      (node (ref "U$5") (pin "39_P3.4/UCA0TXD/UCA0SIMO") (pinfunction "P3.4/UCA0TXD/UCA0SIMO_39_P3.4/UCA0TXD/UCA0SIMO") (pintype "bidirectional"))
    )
    (net (code "106") (name "unconnected-(U$5-P3.5{slash}UCA0RXD{slash}UCA0SOMI-Pad40_P3.5{slash}UCA0RXD{slash}UCA0SOMI)") (class "Default")
      (node (ref "U$5") (pin "40_P3.5/UCA0RXD/UCA0SOMI") (pinfunction "P3.5/UCA0RXD/UCA0SOMI_40_P3.5/UCA0RXD/UCA0SOMI") (pintype "bidirectional"))
    )
    (net (code "107") (name "unconnected-(U$5-P3.6{slash}UCB1STE{slash}UCA1CLK-Pad41_P3.6{slash}UCB1STE{slash}UCA1CLK)") (class "Default")
      (node (ref "U$5") (pin "41_P3.6/UCB1STE/UCA1CLK") (pinfunction "P3.6/UCB1STE/UCA1CLK_41_P3.6/UCB1STE/UCA1CLK") (pintype "bidirectional"))
    )
    (net (code "108") (name "unconnected-(U$5-P4.4{slash}TB0.4-Pad47_P4.4{slash}TB0.4)") (class "Default")
      (node (ref "U$5") (pin "47_P4.4/TB0.4") (pinfunction "P4.4/TB0.4_47_P4.4/TB0.4") (pintype "bidirectional"))
    )
    (net (code "109") (name "unconnected-(U$5-P4.5{slash}TB0.5-Pad48_P4.5{slash}TB0.5)") (class "Default")
      (node (ref "U$5") (pin "48_P4.5/TB0.5") (pinfunction "P4.5/TB0.5_48_P4.5/TB0.5") (pintype "bidirectional"))
    )
    (net (code "110") (name "unconnected-(U$5-P4.6{slash}TB0.6-Pad49_P4.6{slash}TB0.6)") (class "Default")
      (node (ref "U$5") (pin "49_P4.6/TB0.6") (pinfunction "P4.6/TB0.6_49_P4.6/TB0.6") (pintype "bidirectional"))
    )
    (net (code "111") (name "unconnected-(U$5-P4.7{slash}TB0CLK{slash}SMCLK-Pad50_P4.7{slash}TB0CLK{slash}SMCLK)") (class "Default")
      (node (ref "U$5") (pin "50_P4.7/TB0CLK/SMCLK") (pinfunction "P4.7/TB0CLK/SMCLK_50_P4.7/TB0CLK/SMCLK") (pintype "bidirectional"))
    )
    (net (code "112") (name "unconnected-(U$5-P5.0{slash}A8{slash}VREF+{slash}VEREF+-Pad9_P5.0{slash}A8{slash}VREF+{slash}VEREF+)") (class "Default")
      (node (ref "U$5") (pin "9_P5.0/A8/VREF+/VEREF+") (pinfunction "P5.0/A8/VREF+/VEREF+_9_P5.0/A8/VREF+/VEREF+") (pintype "bidirectional"))
    )
    (net (code "113") (name "unconnected-(U$5-P5.1{slash}A9{slash}VREF-{slash}VEREF--Pad10_P5.1{slash}A9{slash}VREF-{slash}VEREF-)") (class "Default")
      (node (ref "U$5") (pin "10_P5.1/A9/VREF-/VEREF-") (pinfunction "P5.1/A9/VREF-/VEREF-_10_P5.1/A9/VREF-/VEREF-") (pintype "bidirectional"))
    )
    (net (code "114") (name "unconnected-(U$5-P5.2{slash}XT2IN-Pad89_P5.2{slash}XT2IN)") (class "Default")
      (node (ref "U$5") (pin "89_P5.2/XT2IN") (pinfunction "P5.2/XT2IN_89_P5.2/XT2IN") (pintype "bidirectional"))
    )
    (net (code "115") (name "unconnected-(U$5-P5.3{slash}XT2OUT-Pad90_P5.3{slash}XT2OUT)") (class "Default")
      (node (ref "U$5") (pin "90_P5.3/XT2OUT") (pinfunction "P5.3/XT2OUT_90_P5.3/XT2OUT") (pintype "bidirectional"))
    )
    (net (code "116") (name "unconnected-(U$5-P5.6{slash}UCA1TXD{slash}UCA1SIMO-Pad53_P5.6{slash}UCA1TXD{slash}UCA1SIMO)") (class "Default")
      (node (ref "U$5") (pin "53_P5.6/UCA1TXD/UCA1SIMO") (pinfunction "P5.6/UCA1TXD/UCA1SIMO_53_P5.6/UCA1TXD/UCA1SIMO") (pintype "bidirectional"))
    )
    (net (code "117") (name "unconnected-(U$5-P5.7{slash}UCA1RXD{slash}UCA1SOMI-Pad54_P5.7{slash}UCA1RXD{slash}UCA1SOMI)") (class "Default")
      (node (ref "U$5") (pin "54_P5.7/UCA1RXD/UCA1SOMI") (pinfunction "P5.7/UCA1RXD/UCA1SOMI_54_P5.7/UCA1RXD/UCA1SOMI") (pintype "bidirectional"))
    )
    (net (code "118") (name "unconnected-(U$5-P6.1{slash}A1-Pad98_P6.1{slash}A1)") (class "Default")
      (node (ref "U$5") (pin "98_P6.1/A1") (pinfunction "P6.1/A1_98_P6.1/A1") (pintype "bidirectional"))
    )
    (net (code "119") (name "unconnected-(U$5-P6.2{slash}A2-Pad99_P6.2{slash}A2)") (class "Default")
      (node (ref "U$5") (pin "99_P6.2/A2") (pinfunction "P6.2/A2_99_P6.2/A2") (pintype "bidirectional"))
    )
    (net (code "120") (name "unconnected-(U$5-P6.6{slash}A6-Pad3_P6.6{slash}A6)") (class "Default")
      (node (ref "U$5") (pin "3_P6.6/A6") (pinfunction "P6.6/A6_3_P6.6/A6") (pintype "bidirectional"))
    )
    (net (code "121") (name "unconnected-(U$5-P6.7{slash}A7-Pad4_P6.7{slash}A7)") (class "Default")
      (node (ref "U$5") (pin "4_P6.7/A7") (pinfunction "P6.7/A7_4_P6.7/A7") (pintype "bidirectional"))
    )
    (net (code "122") (name "unconnected-(U$5-P7.0{slash}XIN-Pad13_P7.0{slash}XIN)") (class "Default")
      (node (ref "U$5") (pin "13_P7.0/XIN") (pinfunction "P7.0/XIN_13_P7.0/XIN") (pintype "bidirectional"))
    )
    (net (code "123") (name "unconnected-(U$5-P7.1{slash}XOUT-Pad14_P7.1{slash}XOUT)") (class "Default")
      (node (ref "U$5") (pin "14_P7.1/XOUT") (pinfunction "P7.1/XOUT_14_P7.1/XOUT") (pintype "bidirectional"))
    )
    (net (code "124") (name "unconnected-(U$5-P7.2{slash}TB0OUTH{slash}SVMOUT-Pad55_P7.2{slash}TB0OUTH{slash}SVMOUT)") (class "Default")
      (node (ref "U$5") (pin "55_P7.2/TB0OUTH/SVMOUT") (pinfunction "P7.2/TB0OUTH/SVMOUT_55_P7.2/TB0OUTH/SVMOUT") (pintype "bidirectional"))
    )
    (net (code "125") (name "unconnected-(U$5-P7.4{slash}A12-Pad5_P7.4{slash}A12)") (class "Default")
      (node (ref "U$5") (pin "5_P7.4/A12") (pinfunction "P7.4/A12_5_P7.4/A12") (pintype "bidirectional"))
    )
    (net (code "126") (name "unconnected-(U$5-P7.5{slash}A13-Pad6_P7.5{slash}A13)") (class "Default")
      (node (ref "U$5") (pin "6_P7.5/A13") (pinfunction "P7.5/A13_6_P7.5/A13") (pintype "bidirectional"))
    )
    (net (code "127") (name "unconnected-(U$5-P7.6{slash}A14-Pad7_P7.6{slash}A14)") (class "Default")
      (node (ref "U$5") (pin "7_P7.6/A14") (pinfunction "P7.6/A14_7_P7.6/A14") (pintype "bidirectional"))
    )
    (net (code "128") (name "unconnected-(U$5-P7.7{slash}A15-Pad8_P7.7{slash}A15)") (class "Default")
      (node (ref "U$5") (pin "8_P7.7/A15") (pinfunction "P7.7/A15_8_P7.7/A15") (pintype "bidirectional"))
    )
    (net (code "129") (name "unconnected-(U$5-P8.4{slash}TA0.4-Pad61_P8.4{slash}TA0.4)") (class "Default")
      (node (ref "U$5") (pin "61_P8.4/TA0.4") (pinfunction "P8.4/TA0.4_61_P8.4/TA0.4") (pintype "bidirectional"))
    )
    (net (code "130") (name "unconnected-(U$5-P8.5{slash}TA1.0-Pad65_P8.5{slash}TA1.0)") (class "Default")
      (node (ref "U$5") (pin "65_P8.5/TA1.0") (pinfunction "P8.5/TA1.0_65_P8.5/TA1.0") (pintype "bidirectional"))
    )
    (net (code "131") (name "unconnected-(U$5-P8.6{slash}TA1.1-Pad66_P8.6{slash}TA1.1)") (class "Default")
      (node (ref "U$5") (pin "66_P8.6/TA1.1") (pinfunction "P8.6/TA1.1_66_P8.6/TA1.1") (pintype "bidirectional"))
    )
    (net (code "132") (name "unconnected-(U$5-P8.7-Pad67_P8.7)") (class "Default")
      (node (ref "U$5") (pin "67_P8.7") (pinfunction "P8.7_67_P8.7") (pintype "bidirectional"))
    )
    (net (code "133") (name "unconnected-(U$5-P9.0{slash}UCB2STE{slash}UCA2CLK-Pad68_P9.0{slash}UCB2STE{slash}UCA2CLK)") (class "Default")
      (node (ref "U$5") (pin "68_P9.0/UCB2STE/UCA2CLK") (pinfunction "P9.0/UCB2STE/UCA2CLK_68_P9.0/UCB2STE/UCA2CLK") (pintype "bidirectional"))
    )
    (net (code "134") (name "unconnected-(U$5-P9.1{slash}UCB2SIMO{slash}UCB2SDA-Pad69_P9.1{slash}UCB2SIMO{slash}UCB2SDA)") (class "Default")
      (node (ref "U$5") (pin "69_P9.1/UCB2SIMO/UCB2SDA") (pinfunction "P9.1/UCB2SIMO/UCB2SDA_69_P9.1/UCB2SIMO/UCB2SDA") (pintype "bidirectional"))
    )
    (net (code "135") (name "unconnected-(U$5-P9.2{slash}UCB2SOMI{slash}UCB2SCL-Pad70_P9.2{slash}UCB2SOMI{slash}UCB2SCL)") (class "Default")
      (node (ref "U$5") (pin "70_P9.2/UCB2SOMI/UCB2SCL") (pinfunction "P9.2/UCB2SOMI/UCB2SCL_70_P9.2/UCB2SOMI/UCB2SCL") (pintype "bidirectional"))
    )
    (net (code "136") (name "unconnected-(U$5-P9.3{slash}UCB2CLK{slash}UCA2STE-Pad71_P9.3{slash}UCB2CLK{slash}UCA2STE)") (class "Default")
      (node (ref "U$5") (pin "71_P9.3/UCB2CLK/UCA2STE") (pinfunction "P9.3/UCB2CLK/UCA2STE_71_P9.3/UCB2CLK/UCA2STE") (pintype "bidirectional"))
    )
    (net (code "137") (name "unconnected-(U$5-P9.6-Pad74_P9.6)") (class "Default")
      (node (ref "U$5") (pin "74_P9.6") (pinfunction "P9.6_74_P9.6") (pintype "bidirectional"))
    )
    (net (code "138") (name "unconnected-(U$5-P9.7-Pad75_P9.7)") (class "Default")
      (node (ref "U$5") (pin "75_P9.7") (pinfunction "P9.7_75_P9.7") (pintype "bidirectional"))
    )
    (net (code "139") (name "unconnected-(U$5-P10.0{slash}UCB3STE{slash}UCA3CLK-Pad76_P10.0{slash}UCB3STE{slash}UCA3CLK)") (class "Default")
      (node (ref "U$5") (pin "76_P10.0/UCB3STE/UCA3CLK") (pinfunction "P10.0/UCB3STE/UCA3CLK_76_P10.0/UCB3STE/UCA3CLK") (pintype "bidirectional"))
    )
    (net (code "140") (name "unconnected-(U$5-P10.4{slash}UCA3TXD{slash}UCA3SIMO-Pad80_P10.4{slash}UCA3TXD{slash}UCA3SIMO)") (class "Default")
      (node (ref "U$5") (pin "80_P10.4/UCA3TXD/UCA3SIMO") (pinfunction "P10.4/UCA3TXD/UCA3SIMO_80_P10.4/UCA3TXD/UCA3SIMO") (pintype "bidirectional"))
    )
    (net (code "141") (name "unconnected-(U$5-P10.6-Pad82_P10.6)") (class "Default")
      (node (ref "U$5") (pin "82_P10.6") (pinfunction "P10.6_82_P10.6") (pintype "bidirectional"))
    )
    (net (code "142") (name "unconnected-(U$11-Pad1)") (class "Default")
      (node (ref "U$11") (pin "1") (pinfunction "1_1") (pintype "bidirectional"))
    )
    (net (code "143") (name "unconnected-(U$11-Pad2)") (class "Default")
      (node (ref "U$11") (pin "2") (pinfunction "2_2") (pintype "bidirectional"))
    )
    (net (code "144") (name "unconnected-(U$11-Pad3)") (class "Default")
      (node (ref "U$11") (pin "3") (pinfunction "3_3") (pintype "bidirectional"))
    )
    (net (code "145") (name "unconnected-(U$11-Pad4)") (class "Default")
      (node (ref "U$11") (pin "4") (pinfunction "4_4") (pintype "bidirectional"))
    )
    (net (code "146") (name "unconnected-(U$12-Pad1)") (class "Default")
      (node (ref "U$12") (pin "1") (pinfunction "1_1") (pintype "bidirectional"))
    )
    (net (code "147") (name "unconnected-(U$12-Pad2)") (class "Default")
      (node (ref "U$12") (pin "2") (pinfunction "2_2") (pintype "bidirectional"))
    )
    (net (code "148") (name "unconnected-(U$12-Pad3)") (class "Default")
      (node (ref "U$12") (pin "3") (pinfunction "3_3") (pintype "bidirectional"))
    )
    (net (code "149") (name "unconnected-(U$12-Pad4)") (class "Default")
      (node (ref "U$12") (pin "4") (pinfunction "4_4") (pintype "bidirectional"))
    )
    (net (code "150") (name "unconnected-(U$16-UART_CTS{slash}SPI_CLK{slash}I2C_SCL-Pad10_UART_CTS{slash}SPI_CLK{slash}I2C_SCL)") (class "Default")
      (node (ref "U$16") (pin "10_UART_CTS/SPI_CLK/I2C_SCL") (pinfunction "UART_CTS/SPI_CLK/I2C_SCL_10_UART_CTS/SPI_CLK/I2C_SCL") (pintype "bidirectional"))
    )
    (net (code "151") (name "unconnected-(U$16-UART_RTS-Pad13_UART_RTS)") (class "Default")
      (node (ref "U$16") (pin "13_UART_RTS") (pinfunction "UART_RTS_13_UART_RTS") (pintype "bidirectional"))
    )
    (net (code "152") (name "unconnected-(U$16-UART_RXD{slash}SPI_SIMO-Pad14_UART_RXD{slash}SPI_SIMO)") (class "Default")
      (node (ref "U$16") (pin "14_UART_RXD/SPI_SIMO") (pinfunction "UART_RXD/SPI_SIMO_14_UART_RXD/SPI_SIMO") (pintype "bidirectional"))
    )
    (net (code "153") (name "unconnected-(U$16-UART_TXD{slash}SPI_SOMI{slash}I2C_SDA-Pad12_UART_TXD{slash}SPI_SOMI{slash}I2C_SDA)") (class "Default")
      (node (ref "U$16") (pin "12_UART_TXD/SPI_SOMI/I2C_SDA") (pinfunction "UART_TXD/SPI_SOMI/I2C_SDA_12_UART_TXD/SPI_SOMI/I2C_SDA") (pintype "bidirectional"))
    )
    (net (code "154") (name "unconnected-(U$16-VCC_TOOL-Pad2_VCC_TOOL)") (class "Default")
      (node (ref "U$16") (pin "2_VCC_TOOL") (pinfunction "VCC_TOOL_2_VCC_TOOL") (pintype "bidirectional"))
    )
  )
)
